# teemsyUp.net
KiCad netlist of a schematic drawn in EAGLE
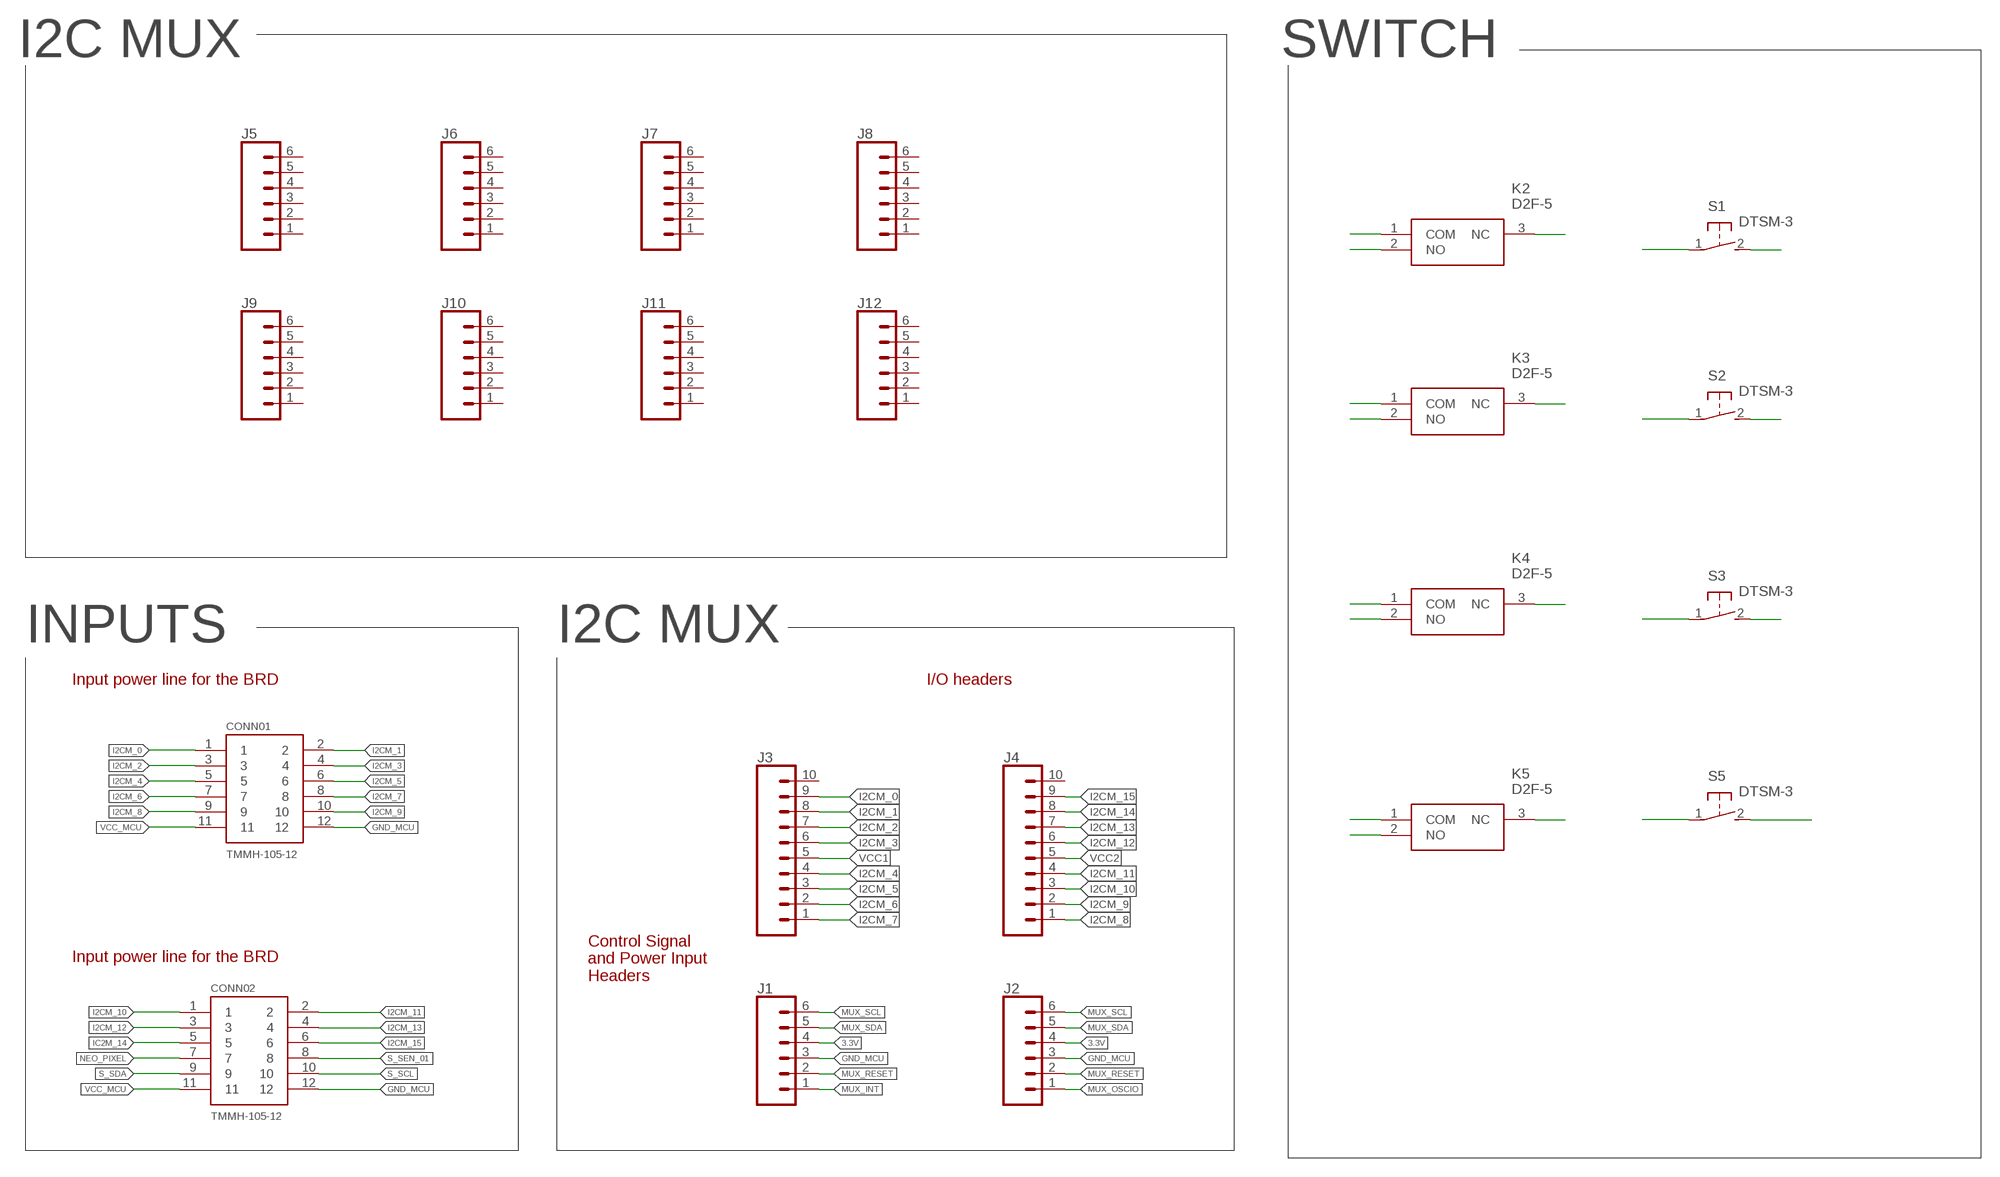
[diagram p0: schematic, sheet 1]

(export (version "E")
  (design (tool "Eeschema 10.0.6"))
  (components
    (comp (ref "CONN01")
      (value "TMMH-105-12")
      (footprint "eagle-import:TMMH-105-12")
      (libsource (lib "eagle-import") (part "TMMH-105-12"))
    )
    (comp (ref "CONN02")
      (value "TMMH-105-12")
      (footprint "eagle-import:TMMH-105-12")
      (libsource (lib "eagle-import") (part "TMMH-105-12"))
    )
    (comp (ref "J1")
      (value "CONN_06SMD_MALE")
      (footprint "eagle-import:1X06_SMD_MALE")
      (libsource (lib "eagle-import") (part "CONN_06SMD_MALE"))
    )
    (comp (ref "J2")
      (value "CONN_06SMD_MALE")
      (footprint "eagle-import:1X06_SMD_MALE")
      (libsource (lib "eagle-import") (part "CONN_06SMD_MALE"))
    )
    (comp (ref "J3")
      (value "CONN_10SMD_MALE")
      (footprint "eagle-import:1X10_SMD_MALE")
      (libsource (lib "eagle-import") (part "CONN_10SMD_MALE"))
    )
    (comp (ref "J4")
      (value "CONN_10SMD_MALE")
      (footprint "eagle-import:1X10_SMD_MALE")
      (libsource (lib "eagle-import") (part "CONN_10SMD_MALE"))
    )
    (comp (ref "J5")
      (value "CONN_06SMD-1MM")
      (footprint "eagle-import:1X06-1MM")
      (libsource (lib "eagle-import") (part "CONN_06SMD-1MM"))
    )
    (comp (ref "J6")
      (value "CONN_06SMD-1MM")
      (footprint "eagle-import:1X06-1MM")
      (libsource (lib "eagle-import") (part "CONN_06SMD-1MM"))
    )
    (comp (ref "J7")
      (value "CONN_06SMD-1MM")
      (footprint "eagle-import:1X06-1MM")
      (libsource (lib "eagle-import") (part "CONN_06SMD-1MM"))
    )
    (comp (ref "J8")
      (value "CONN_06SMD-1MM")
      (footprint "eagle-import:1X06-1MM")
      (libsource (lib "eagle-import") (part "CONN_06SMD-1MM"))
    )
    (comp (ref "J9")
      (value "CONN_06SMD-1MM")
      (footprint "eagle-import:1X06-1MM")
      (libsource (lib "eagle-import") (part "CONN_06SMD-1MM"))
    )
    (comp (ref "J10")
      (value "CONN_06SMD-1MM")
      (footprint "eagle-import:1X06-1MM")
      (libsource (lib "eagle-import") (part "CONN_06SMD-1MM"))
    )
    (comp (ref "J11")
      (value "CONN_06SMD-1MM")
      (footprint "eagle-import:1X06-1MM")
      (libsource (lib "eagle-import") (part "CONN_06SMD-1MM"))
    )
    (comp (ref "J12")
      (value "CONN_06SMD-1MM")
      (footprint "eagle-import:1X06-1MM")
      (libsource (lib "eagle-import") (part "CONN_06SMD-1MM"))
    )
    (comp (ref "K2")
      (value "D2F-5")
      (footprint "eagle-import:SHDR3W100P0X508_1X3_1280X580X5")
      (fields (field (name "MOUSER_PART_NUMBER") "653-D2F-5"))
      (libsource (lib "eagle-import") (part "D2F-5"))
    )
    (comp (ref "K3")
      (value "D2F-5")
      (footprint "eagle-import:SHDR3W100P0X508_1X3_1280X580X5")
      (fields (field (name "MOUSER_PART_NUMBER") "653-D2F-5"))
      (libsource (lib "eagle-import") (part "D2F-5"))
    )
    (comp (ref "K4")
      (value "D2F-5")
      (footprint "eagle-import:SHDR3W100P0X508_1X3_1280X580X5")
      (fields (field (name "MOUSER_PART_NUMBER") "653-D2F-5"))
      (libsource (lib "eagle-import") (part "D2F-5"))
    )
    (comp (ref "K5")
      (value "D2F-5")
      (footprint "eagle-import:SHDR3W100P0X508_1X3_1280X580X5")
      (fields (field (name "MOUSER_PART_NUMBER") "653-D2F-5"))
      (libsource (lib "eagle-import") (part "D2F-5"))
    )
    (comp (ref "S1")
      (value "DTSM-3")
      (footprint "eagle-import:DTSM-3")
      (libsource (lib "eagle-import") (part "DTSM-3"))
    )
    (comp (ref "S2")
      (value "DTSM-3")
      (footprint "eagle-import:DTSM-3")
      (libsource (lib "eagle-import") (part "DTSM-3"))
    )
    (comp (ref "S3")
      (value "DTSM-3")
      (footprint "eagle-import:DTSM-3")
      (libsource (lib "eagle-import") (part "DTSM-3"))
    )
    (comp (ref "S5")
      (value "DTSM-3")
      (footprint "eagle-import:DTSM-3")
      (libsource (lib "eagle-import") (part "DTSM-3"))
    )
  )
  (nets
    (net (code "1") (name "3.3V") (class "Default")
      (node (ref "J1") (pin "4") (pinfunction "4_4") (pintype "passive"))
      (node (ref "J2") (pin "4") (pinfunction "4_4") (pintype "passive"))
    )
    (net (code "2") (name "GND_MCU") (class "Default")
      (node (ref "CONN01") (pin "12") (pinfunction "12_12") (pintype "bidirectional"))
      (node (ref "CONN02") (pin "12") (pinfunction "12_12") (pintype "bidirectional"))
      (node (ref "J1") (pin "3") (pinfunction "3_3") (pintype "passive"))
      (node (ref "J2") (pin "3") (pinfunction "3_3") (pintype "passive"))
    )
    (net (code "3") (name "I2CM_0") (class "Default")
      (node (ref "CONN01") (pin "1") (pinfunction "1_1") (pintype "bidirectional"))
      (node (ref "J3") (pin "9") (pinfunction "9_9") (pintype "passive"))
    )
    (net (code "4") (name "I2CM_1") (class "Default")
      (node (ref "CONN01") (pin "2") (pinfunction "2_2") (pintype "bidirectional"))
      (node (ref "J3") (pin "8") (pinfunction "8_8") (pintype "passive"))
    )
    (net (code "5") (name "I2CM_2") (class "Default")
      (node (ref "CONN01") (pin "3") (pinfunction "3_3") (pintype "bidirectional"))
      (node (ref "J3") (pin "7") (pinfunction "7_7") (pintype "passive"))
    )
    (net (code "6") (name "I2CM_3") (class "Default")
      (node (ref "CONN01") (pin "4") (pinfunction "4_4") (pintype "bidirectional"))
      (node (ref "J3") (pin "6") (pinfunction "6_6") (pintype "passive"))
    )
    (net (code "7") (name "I2CM_4") (class "Default")
      (node (ref "CONN01") (pin "5") (pinfunction "5_5") (pintype "bidirectional"))
      (node (ref "J3") (pin "4") (pinfunction "4_4") (pintype "passive"))
    )
    (net (code "8") (name "I2CM_5") (class "Default")
      (node (ref "CONN01") (pin "6") (pinfunction "6_6") (pintype "bidirectional"))
      (node (ref "J3") (pin "3") (pinfunction "3_3") (pintype "passive"))
    )
    (net (code "9") (name "I2CM_6") (class "Default")
      (node (ref "CONN01") (pin "7") (pinfunction "7_7") (pintype "bidirectional"))
      (node (ref "J3") (pin "2") (pinfunction "2_2") (pintype "passive"))
    )
    (net (code "10") (name "I2CM_7") (class "Default")
      (node (ref "CONN01") (pin "8") (pinfunction "8_8") (pintype "bidirectional"))
      (node (ref "J3") (pin "1") (pinfunction "1_1") (pintype "passive"))
    )
    (net (code "11") (name "I2CM_8") (class "Default")
      (node (ref "CONN01") (pin "9") (pinfunction "9_9") (pintype "bidirectional"))
      (node (ref "J4") (pin "1") (pinfunction "1_1") (pintype "passive"))
    )
    (net (code "12") (name "I2CM_9") (class "Default")
      (node (ref "CONN01") (pin "10") (pinfunction "10_10") (pintype "bidirectional"))
      (node (ref "J4") (pin "2") (pinfunction "2_2") (pintype "passive"))
    )
    (net (code "13") (name "I2CM_10") (class "Default")
      (node (ref "CONN02") (pin "1") (pinfunction "1_1") (pintype "bidirectional"))
      (node (ref "J4") (pin "3") (pinfunction "3_3") (pintype "passive"))
    )
    (net (code "14") (name "I2CM_11") (class "Default")
      (node (ref "CONN02") (pin "2") (pinfunction "2_2") (pintype "bidirectional"))
      (node (ref "J4") (pin "4") (pinfunction "4_4") (pintype "passive"))
    )
    (net (code "15") (name "I2CM_12") (class "Default")
      (node (ref "CONN02") (pin "3") (pinfunction "3_3") (pintype "bidirectional"))
      (node (ref "J4") (pin "6") (pinfunction "6_6") (pintype "passive"))
    )
    (net (code "16") (name "I2CM_13") (class "Default")
      (node (ref "CONN02") (pin "4") (pinfunction "4_4") (pintype "bidirectional"))
      (node (ref "J4") (pin "7") (pinfunction "7_7") (pintype "passive"))
    )
    (net (code "17") (name "I2CM_14") (class "Default")
      (node (ref "J4") (pin "8") (pinfunction "8_8") (pintype "passive"))
    )
    (net (code "18") (name "I2CM_15") (class "Default")
      (node (ref "CONN02") (pin "6") (pinfunction "6_6") (pintype "bidirectional"))
      (node (ref "J4") (pin "9") (pinfunction "9_9") (pintype "passive"))
    )
    (net (code "19") (name "IC2M_14") (class "Default")
      (node (ref "CONN02") (pin "5") (pinfunction "5_5") (pintype "bidirectional"))
    )
    (net (code "20") (name "MUX_INT") (class "Default")
      (node (ref "J1") (pin "1") (pinfunction "1_1") (pintype "passive"))
    )
    (net (code "21") (name "MUX_OSCIO") (class "Default")
      (node (ref "J2") (pin "1") (pinfunction "1_1") (pintype "passive"))
    )
    (net (code "22") (name "MUX_RESET") (class "Default")
      (node (ref "J1") (pin "2") (pinfunction "2_2") (pintype "passive"))
      (node (ref "J2") (pin "2") (pinfunction "2_2") (pintype "passive"))
    )
    (net (code "23") (name "MUX_SCL") (class "Default")
      (node (ref "J1") (pin "6") (pinfunction "6_6") (pintype "passive"))
      (node (ref "J2") (pin "6") (pinfunction "6_6") (pintype "passive"))
    )
    (net (code "24") (name "MUX_SDA") (class "Default")
      (node (ref "J1") (pin "5") (pinfunction "5_5") (pintype "passive"))
      (node (ref "J2") (pin "5") (pinfunction "5_5") (pintype "passive"))
    )
    (net (code "25") (name "NEO_PIXEL") (class "Default")
      (node (ref "CONN02") (pin "7") (pinfunction "7_7") (pintype "bidirectional"))
    )
    (net (code "26") (name "S_SCL") (class "Default")
      (node (ref "CONN02") (pin "10") (pinfunction "10_10") (pintype "bidirectional"))
    )
    (net (code "27") (name "S_SDA") (class "Default")
      (node (ref "CONN02") (pin "9") (pinfunction "9_9") (pintype "bidirectional"))
    )
    (net (code "28") (name "S_SEN_01") (class "Default")
      (node (ref "CONN02") (pin "8") (pinfunction "8_8") (pintype "bidirectional"))
    )
    (net (code "29") (name "VCC1") (class "Default")
      (node (ref "J3") (pin "5") (pinfunction "5_5") (pintype "passive"))
    )
    (net (code "30") (name "VCC2") (class "Default")
      (node (ref "J4") (pin "5") (pinfunction "5_5") (pintype "passive"))
    )
    (net (code "31") (name "VCC_MCU") (class "Default")
      (node (ref "CONN01") (pin "11") (pinfunction "11_11") (pintype "bidirectional"))
      (node (ref "CONN02") (pin "11") (pinfunction "11_11") (pintype "bidirectional"))
    )
    (net (code "32") (name "unconnected-(J3-Pad10)") (class "Default")
      (node (ref "J3") (pin "10") (pinfunction "10_10") (pintype "passive"))
    )
    (net (code "33") (name "unconnected-(J4-Pad10)") (class "Default")
      (node (ref "J4") (pin "10") (pinfunction "10_10") (pintype "passive"))
    )
    (net (code "34") (name "unconnected-(J5-Pad1)") (class "Default")
      (node (ref "J5") (pin "1") (pinfunction "1_1") (pintype "passive"))
    )
    (net (code "35") (name "unconnected-(J5-Pad2)") (class "Default")
      (node (ref "J5") (pin "2") (pinfunction "2_2") (pintype "passive"))
    )
    (net (code "36") (name "unconnected-(J5-Pad3)") (class "Default")
      (node (ref "J5") (pin "3") (pinfunction "3_3") (pintype "passive"))
    )
    (net (code "37") (name "unconnected-(J5-Pad4)") (class "Default")
      (node (ref "J5") (pin "4") (pinfunction "4_4") (pintype "passive"))
    )
    (net (code "38") (name "unconnected-(J5-Pad5)") (class "Default")
      (node (ref "J5") (pin "5") (pinfunction "5_5") (pintype "passive"))
    )
    (net (code "39") (name "unconnected-(J5-Pad6)") (class "Default")
      (node (ref "J5") (pin "6") (pinfunction "6_6") (pintype "passive"))
    )
    (net (code "40") (name "unconnected-(J6-Pad1)") (class "Default")
      (node (ref "J6") (pin "1") (pinfunction "1_1") (pintype "passive"))
    )
    (net (code "41") (name "unconnected-(J6-Pad2)") (class "Default")
      (node (ref "J6") (pin "2") (pinfunction "2_2") (pintype "passive"))
    )
    (net (code "42") (name "unconnected-(J6-Pad3)") (class "Default")
      (node (ref "J6") (pin "3") (pinfunction "3_3") (pintype "passive"))
    )
    (net (code "43") (name "unconnected-(J6-Pad4)") (class "Default")
      (node (ref "J6") (pin "4") (pinfunction "4_4") (pintype "passive"))
    )
    (net (code "44") (name "unconnected-(J6-Pad5)") (class "Default")
      (node (ref "J6") (pin "5") (pinfunction "5_5") (pintype "passive"))
    )
    (net (code "45") (name "unconnected-(J6-Pad6)") (class "Default")
      (node (ref "J6") (pin "6") (pinfunction "6_6") (pintype "passive"))
    )
    (net (code "46") (name "unconnected-(J7-Pad1)") (class "Default")
      (node (ref "J7") (pin "1") (pinfunction "1_1") (pintype "passive"))
    )
    (net (code "47") (name "unconnected-(J7-Pad2)") (class "Default")
      (node (ref "J7") (pin "2") (pinfunction "2_2") (pintype "passive"))
    )
    (net (code "48") (name "unconnected-(J7-Pad3)") (class "Default")
      (node (ref "J7") (pin "3") (pinfunction "3_3") (pintype "passive"))
    )
    (net (code "49") (name "unconnected-(J7-Pad4)") (class "Default")
      (node (ref "J7") (pin "4") (pinfunction "4_4") (pintype "passive"))
    )
    (net (code "50") (name "unconnected-(J7-Pad5)") (class "Default")
      (node (ref "J7") (pin "5") (pinfunction "5_5") (pintype "passive"))
    )
    (net (code "51") (name "unconnected-(J7-Pad6)") (class "Default")
      (node (ref "J7") (pin "6") (pinfunction "6_6") (pintype "passive"))
    )
    (net (code "52") (name "unconnected-(J8-Pad1)") (class "Default")
      (node (ref "J8") (pin "1") (pinfunction "1_1") (pintype "passive"))
    )
    (net (code "53") (name "unconnected-(J8-Pad2)") (class "Default")
      (node (ref "J8") (pin "2") (pinfunction "2_2") (pintype "passive"))
    )
    (net (code "54") (name "unconnected-(J8-Pad3)") (class "Default")
      (node (ref "J8") (pin "3") (pinfunction "3_3") (pintype "passive"))
    )
    (net (code "55") (name "unconnected-(J8-Pad4)") (class "Default")
      (node (ref "J8") (pin "4") (pinfunction "4_4") (pintype "passive"))
    )
    (net (code "56") (name "unconnected-(J8-Pad5)") (class "Default")
      (node (ref "J8") (pin "5") (pinfunction "5_5") (pintype "passive"))
    )
    (net (code "57") (name "unconnected-(J8-Pad6)") (class "Default")
      (node (ref "J8") (pin "6") (pinfunction "6_6") (pintype "passive"))
    )
    (net (code "58") (name "unconnected-(J9-Pad1)") (class "Default")
      (node (ref "J9") (pin "1") (pinfunction "1_1") (pintype "passive"))
    )
    (net (code "59") (name "unconnected-(J9-Pad2)") (class "Default")
      (node (ref "J9") (pin "2") (pinfunction "2_2") (pintype "passive"))
    )
    (net (code "60") (name "unconnected-(J9-Pad3)") (class "Default")
      (node (ref "J9") (pin "3") (pinfunction "3_3") (pintype "passive"))
    )
    (net (code "61") (name "unconnected-(J9-Pad4)") (class "Default")
      (node (ref "J9") (pin "4") (pinfunction "4_4") (pintype "passive"))
    )
    (net (code "62") (name "unconnected-(J9-Pad5)") (class "Default")
      (node (ref "J9") (pin "5") (pinfunction "5_5") (pintype "passive"))
    )
    (net (code "63") (name "unconnected-(J9-Pad6)") (class "Default")
      (node (ref "J9") (pin "6") (pinfunction "6_6") (pintype "passive"))
    )
    (net (code "64") (name "unconnected-(J10-Pad1)") (class "Default")
      (node (ref "J10") (pin "1") (pinfunction "1_1") (pintype "passive"))
    )
    (net (code "65") (name "unconnected-(J10-Pad2)") (class "Default")
      (node (ref "J10") (pin "2") (pinfunction "2_2") (pintype "passive"))
    )
    (net (code "66") (name "unconnected-(J10-Pad3)") (class "Default")
      (node (ref "J10") (pin "3") (pinfunction "3_3") (pintype "passive"))
    )
    (net (code "67") (name "unconnected-(J10-Pad4)") (class "Default")
      (node (ref "J10") (pin "4") (pinfunction "4_4") (pintype "passive"))
    )
    (net (code "68") (name "unconnected-(J10-Pad5)") (class "Default")
      (node (ref "J10") (pin "5") (pinfunction "5_5") (pintype "passive"))
    )
    (net (code "69") (name "unconnected-(J10-Pad6)") (class "Default")
      (node (ref "J10") (pin "6") (pinfunction "6_6") (pintype "passive"))
    )
    (net (code "70") (name "unconnected-(J11-Pad1)") (class "Default")
      (node (ref "J11") (pin "1") (pinfunction "1_1") (pintype "passive"))
    )
    (net (code "71") (name "unconnected-(J11-Pad2)") (class "Default")
      (node (ref "J11") (pin "2") (pinfunction "2_2") (pintype "passive"))
    )
    (net (code "72") (name "unconnected-(J11-Pad3)") (class "Default")
      (node (ref "J11") (pin "3") (pinfunction "3_3") (pintype "passive"))
    )
    (net (code "73") (name "unconnected-(J11-Pad4)") (class "Default")
      (node (ref "J11") (pin "4") (pinfunction "4_4") (pintype "passive"))
    )
    (net (code "74") (name "unconnected-(J11-Pad5)") (class "Default")
      (node (ref "J11") (pin "5") (pinfunction "5_5") (pintype "passive"))
    )
    (net (code "75") (name "unconnected-(J11-Pad6)") (class "Default")
      (node (ref "J11") (pin "6") (pinfunction "6_6") (pintype "passive"))
    )
    (net (code "76") (name "unconnected-(J12-Pad1)") (class "Default")
      (node (ref "J12") (pin "1") (pinfunction "1_1") (pintype "passive"))
    )
    (net (code "77") (name "unconnected-(J12-Pad2)") (class "Default")
      (node (ref "J12") (pin "2") (pinfunction "2_2") (pintype "passive"))
    )
    (net (code "78") (name "unconnected-(J12-Pad3)") (class "Default")
      (node (ref "J12") (pin "3") (pinfunction "3_3") (pintype "passive"))
    )
    (net (code "79") (name "unconnected-(J12-Pad4)") (class "Default")
      (node (ref "J12") (pin "4") (pinfunction "4_4") (pintype "passive"))
    )
    (net (code "80") (name "unconnected-(J12-Pad5)") (class "Default")
      (node (ref "J12") (pin "5") (pinfunction "5_5") (pintype "passive"))
    )
    (net (code "81") (name "unconnected-(J12-Pad6)") (class "Default")
      (node (ref "J12") (pin "6") (pinfunction "6_6") (pintype "passive"))
    )
    (net (code "82") (name "unconnected-(K2-COM-Pad1)") (class "Default")
      (node (ref "K2") (pin "1") (pinfunction "COM_1") (pintype "bidirectional"))
    )
    (net (code "83") (name "unconnected-(K2-NC-Pad3)") (class "Default")
      (node (ref "K2") (pin "3") (pinfunction "NC_3") (pintype "no_connect"))
    )
    (net (code "84") (name "unconnected-(K2-NO-Pad2)") (class "Default")
      (node (ref "K2") (pin "2") (pinfunction "NO_2") (pintype "bidirectional"))
    )
    (net (code "85") (name "unconnected-(K3-COM-Pad1)") (class "Default")
      (node (ref "K3") (pin "1") (pinfunction "COM_1") (pintype "bidirectional"))
    )
    (net (code "86") (name "unconnected-(K3-NC-Pad3)") (class "Default")
      (node (ref "K3") (pin "3") (pinfunction "NC_3") (pintype "no_connect"))
    )
    (net (code "87") (name "unconnected-(K3-NO-Pad2)") (class "Default")
      (node (ref "K3") (pin "2") (pinfunction "NO_2") (pintype "bidirectional"))
    )
    (net (code "88") (name "unconnected-(K4-COM-Pad1)") (class "Default")
      (node (ref "K4") (pin "1") (pinfunction "COM_1") (pintype "bidirectional"))
    )
    (net (code "89") (name "unconnected-(K4-NC-Pad3)") (class "Default")
      (node (ref "K4") (pin "3") (pinfunction "NC_3") (pintype "no_connect"))
    )
    (net (code "90") (name "unconnected-(K4-NO-Pad2)") (class "Default")
      (node (ref "K4") (pin "2") (pinfunction "NO_2") (pintype "bidirectional"))
    )
    (net (code "91") (name "unconnected-(K5-COM-Pad1)") (class "Default")
      (node (ref "K5") (pin "1") (pinfunction "COM_1") (pintype "bidirectional"))
    )
    (net (code "92") (name "unconnected-(K5-NC-Pad3)") (class "Default")
      (node (ref "K5") (pin "3") (pinfunction "NC_3") (pintype "no_connect"))
    )
    (net (code "93") (name "unconnected-(K5-NO-Pad2)") (class "Default")
      (node (ref "K5") (pin "2") (pinfunction "NO_2") (pintype "bidirectional"))
    )
    (net (code "94") (name "unconnected-(S1-Pad1)") (class "Default")
      (node (ref "S1") (pin "1") (pinfunction "1_1") (pintype "passive"))
    )
    (net (code "95") (name "unconnected-(S1-Pad2)") (class "Default")
      (node (ref "S1") (pin "2") (pinfunction "2_2") (pintype "passive"))
    )
    (net (code "96") (name "unconnected-(S2-Pad1)") (class "Default")
      (node (ref "S2") (pin "1") (pinfunction "1_1") (pintype "passive"))
    )
    (net (code "97") (name "unconnected-(S2-Pad2)") (class "Default")
      (node (ref "S2") (pin "2") (pinfunction "2_2") (pintype "passive"))
    )
    (net (code "98") (name "unconnected-(S3-Pad1)") (class "Default")
      (node (ref "S3") (pin "1") (pinfunction "1_1") (pintype "passive"))
    )
    (net (code "99") (name "unconnected-(S3-Pad2)") (class "Default")
      (node (ref "S3") (pin "2") (pinfunction "2_2") (pintype "passive"))
    )
    (net (code "100") (name "unconnected-(S5-Pad1)") (class "Default")
      (node (ref "S5") (pin "1") (pinfunction "1_1") (pintype "passive"))
    )
    (net (code "101") (name "unconnected-(S5-Pad2)") (class "Default")
      (node (ref "S5") (pin "2") (pinfunction "2_2") (pintype "passive"))
    )
  )
)
